# Example_A.net
KiCad netlist of a schematic drawn in EAGLE
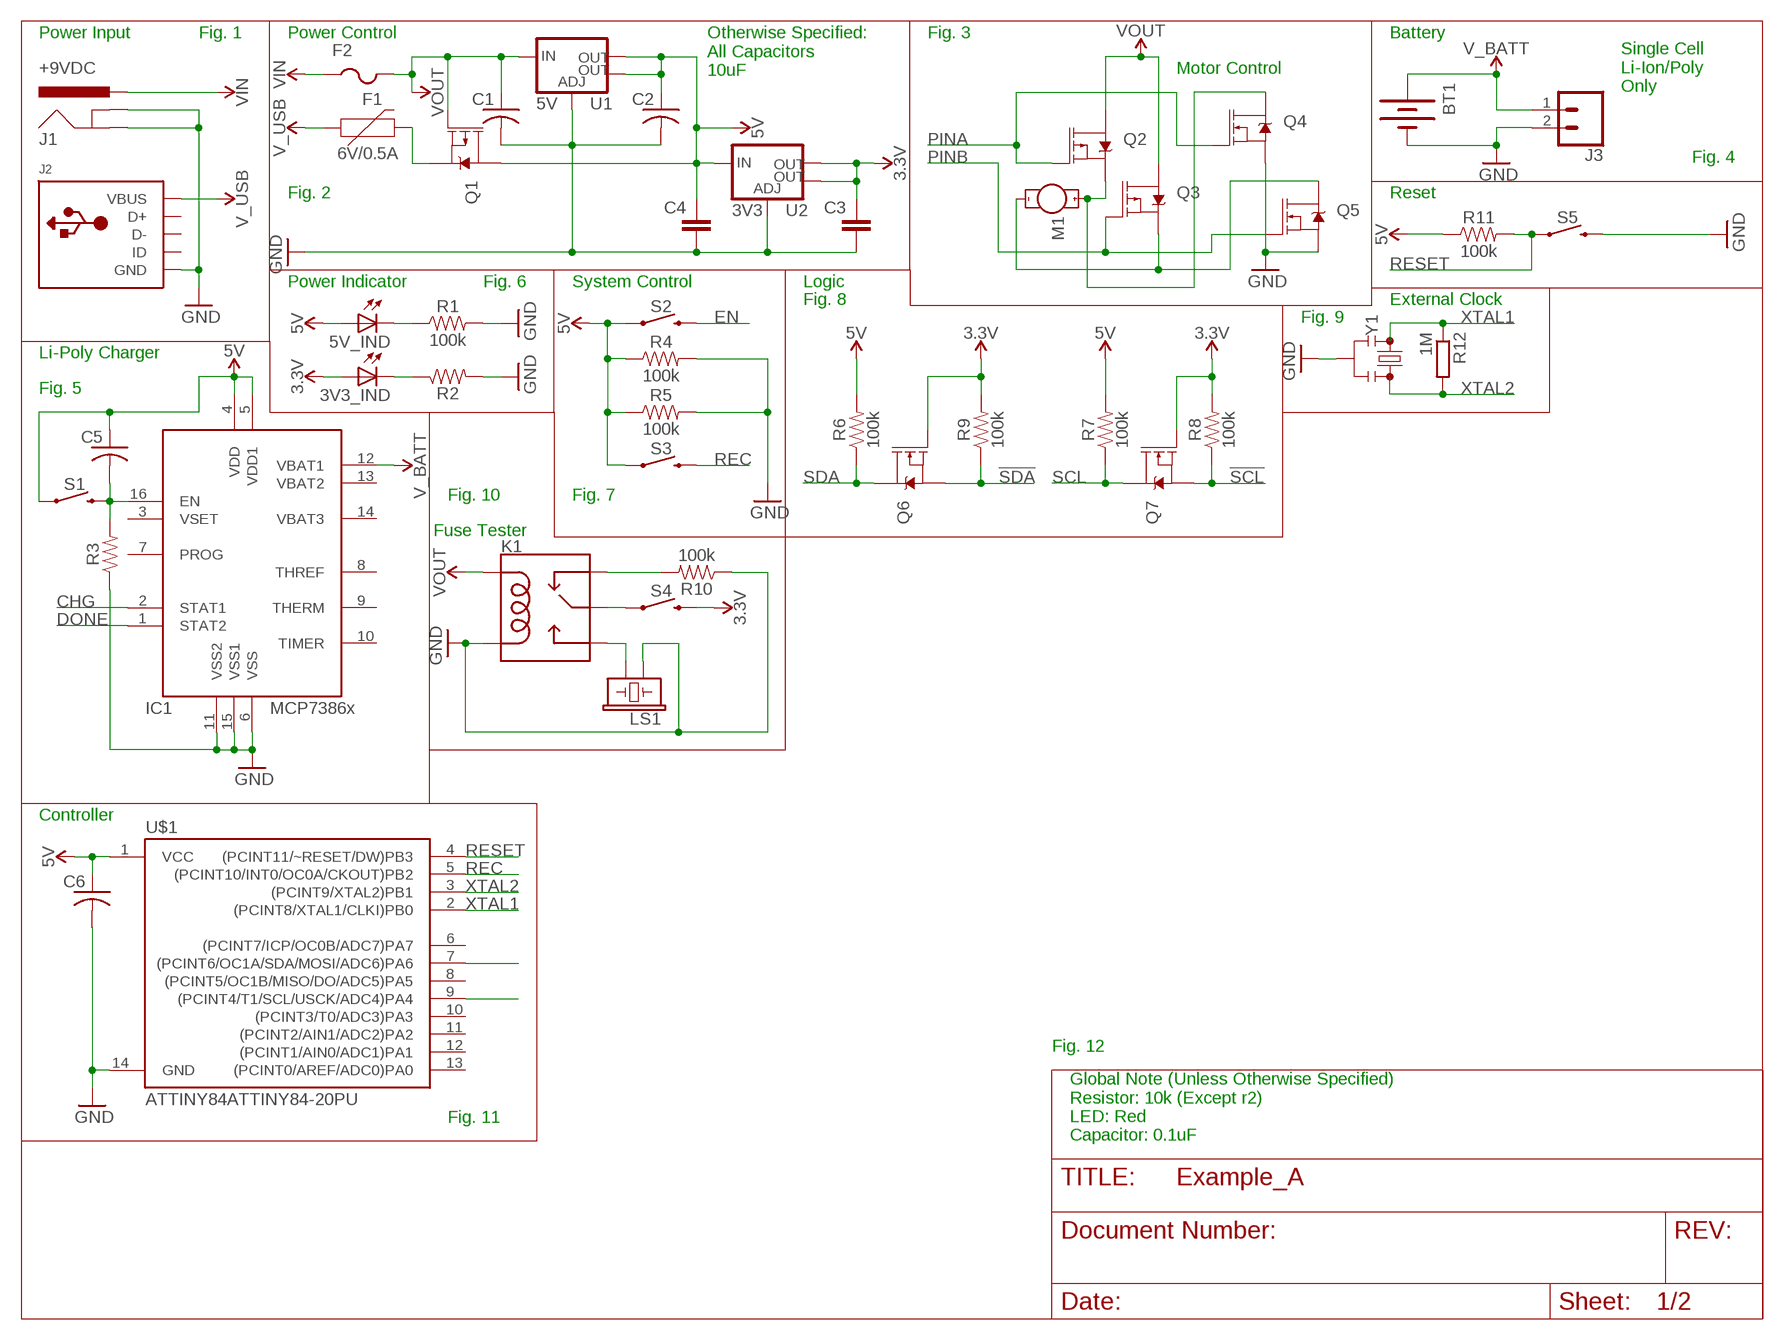
[diagram p0: schematic, sheet 1]
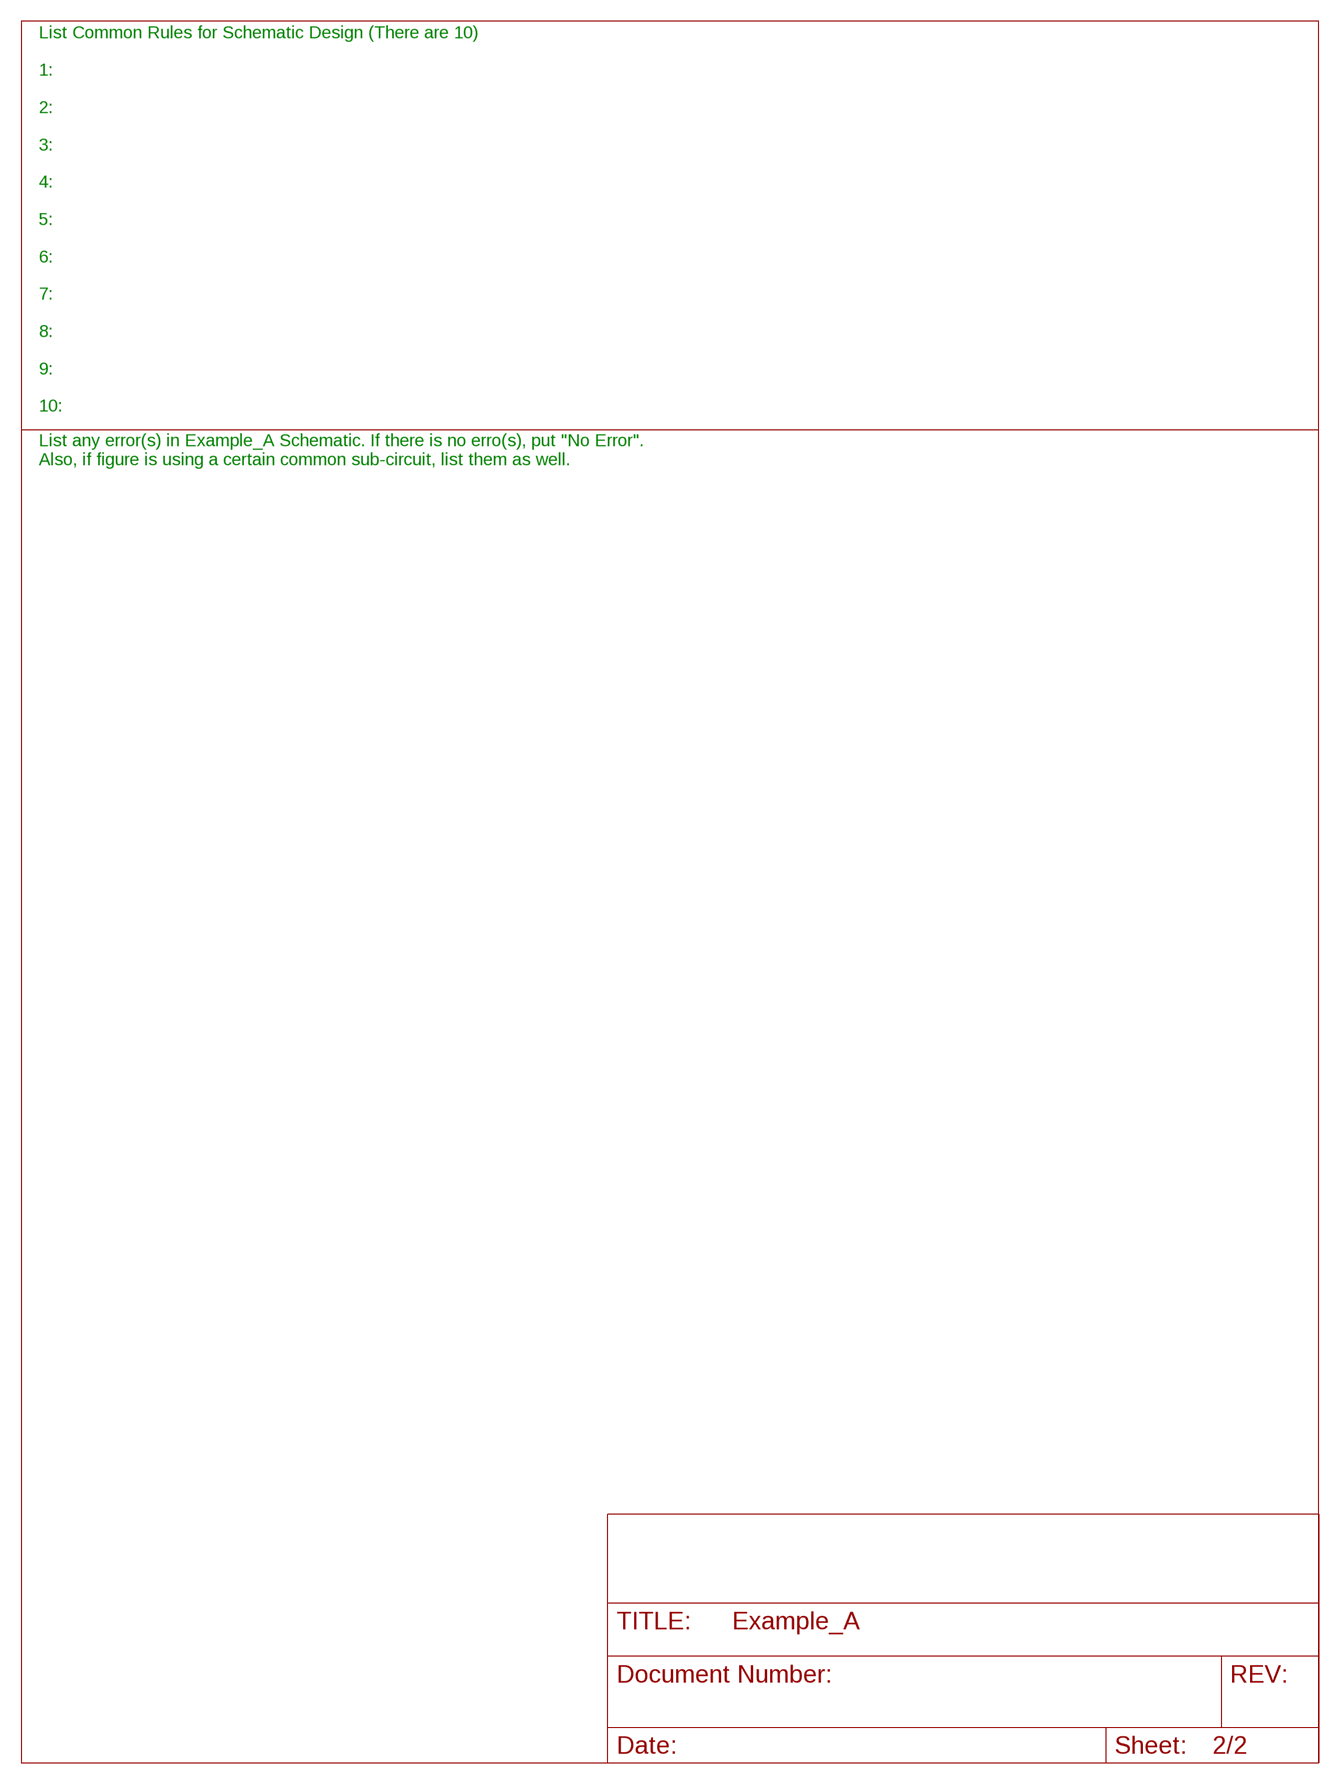
[diagram p1: schematic, sheet 2]

(export (version "E")
  (design (tool "Eeschema 10.0.6"))
  (components
    (comp (ref "3V3_IND")
      (value "LEDCHIP-LED0805")
      (footprint "eagle-import:CHIP-LED0805")
      (libsource (lib "eagle-import") (part "LEDCHIP-LED0805"))
    )
    (comp (ref "5V_IND")
      (value "LEDCHIP-LED0805")
      (footprint "eagle-import:CHIP-LED0805")
      (libsource (lib "eagle-import") (part "LEDCHIP-LED0805"))
    )
    (comp (ref "BT1")
      (value "BATTERYFOB")
      (footprint "eagle-import:BATTERY_20MM_PTH_COMPACT")
      (libsource (lib "eagle-import") (part "BATTERYFOB"))
    )
    (comp (ref "C1")
      (value "C-USC0805")
      (footprint "eagle-import:C0805")
      (libsource (lib "eagle-import") (part "C-USC0805"))
    )
    (comp (ref "C2")
      (value "C-USC0805")
      (footprint "eagle-import:C0805")
      (libsource (lib "eagle-import") (part "C-USC0805"))
    )
    (comp (ref "C3")
      (value "C-EUC0805")
      (footprint "eagle-import:C0805")
      (libsource (lib "eagle-import") (part "C-EUC0805"))
    )
    (comp (ref "C4")
      (value "C-EUC0805")
      (footprint "eagle-import:C0805")
      (libsource (lib "eagle-import") (part "C-EUC0805"))
    )
    (comp (ref "C5")
      (value "C-USC0805")
      (footprint "eagle-import:C0805")
      (libsource (lib "eagle-import") (part "C-USC0805"))
    )
    (comp (ref "C6")
      (value "C-USC0805")
      (footprint "eagle-import:C0805")
      (libsource (lib "eagle-import") (part "C-USC0805"))
    )
    (comp (ref "F1")
      (value "6V/0.5A")
      (footprint "eagle-import:1206")
      (libsource (lib "eagle-import") (part "PPTC_HALF-AMP"))
    )
    (comp (ref "F2")
      (value "PTCFUSE-1206")
      (footprint "eagle-import:R1206")
      (libsource (lib "eagle-import") (part "PTCFUSE-1206"))
    )
    (comp (ref "IC1")
      (value "MCP7386XS")
      (footprint "eagle-import:SO16")
      (libsource (lib "eagle-import") (part "MCP7386XS"))
    )
    (comp (ref "J1")
      (value "+9VDC")
      (footprint "eagle-import:POWER_JACK_SMD")
      (libsource (lib "eagle-import") (part "POWER_JACKSMD"))
    )
    (comp (ref "J2")
      (value "USBMINIB")
      (footprint "eagle-import:USB-MINIB")
      (libsource (lib "eagle-import") (part "USBMINIB"))
    )
    (comp (ref "J3")
      (value "CONN_023.5MM_LOCK")
      (footprint "eagle-import:SCREWTERMINAL-3.5MM-2_LOCK")
      (libsource (lib "eagle-import") (part "CONN_023.5MM_LOCK"))
    )
    (comp (ref "K1")
      (value "RELAY-SPDT-JZC-11F")
      (footprint "eagle-import:RELAY-JZC")
      (libsource (lib "eagle-import") (part "RELAY-SPDT-JZC-11F"))
    )
    (comp (ref "LS1")
      (value "BUZZER-PTH")
      (footprint "eagle-import:BUZZER-12MM")
      (libsource (lib "eagle-import") (part "BUZZER-PTH"))
    )
    (comp (ref "M1")
      (value "MOTOR10MM")
      (footprint "eagle-import:VIBE-MOTOR-10MM")
      (libsource (lib "eagle-import") (part "MOTOR10MM"))
    )
    (comp (ref "Q1")
      (value "MOSFET_PCH-SI2309DS")
      (footprint "eagle-import:SOT23-3")
      (libsource (lib "eagle-import") (part "MOSFET_PCH-SI2309DS"))
    )
    (comp (ref "Q2")
      (value "MOSFET_PCH-SI2309DS")
      (footprint "eagle-import:SOT23-3")
      (libsource (lib "eagle-import") (part "MOSFET_PCH-SI2309DS"))
    )
    (comp (ref "Q3")
      (value "MOSFET_PCH-SI2309DS")
      (footprint "eagle-import:SOT23-3")
      (libsource (lib "eagle-import") (part "MOSFET_PCH-SI2309DS"))
    )
    (comp (ref "Q4")
      (value "MOSFET-NCH-PSMN7R0")
      (footprint "eagle-import:TO-263_D2PAK")
      (libsource (lib "eagle-import") (part "MOSFET-NCH-PSMN7R0"))
    )
    (comp (ref "Q5")
      (value "MOSFET-NCH-PSMN7R0")
      (footprint "eagle-import:TO-263_D2PAK")
      (libsource (lib "eagle-import") (part "MOSFET-NCH-PSMN7R0"))
    )
    (comp (ref "Q6")
      (value "MOSFET-NCH-FQP30N06L")
      (footprint "eagle-import:TO220V")
      (libsource (lib "eagle-import") (part "MOSFET-NCH-FQP30N06L"))
    )
    (comp (ref "Q7")
      (value "MOSFET-NCH-FQP30N06L")
      (footprint "eagle-import:TO220V")
      (libsource (lib "eagle-import") (part "MOSFET-NCH-FQP30N06L"))
    )
    (comp (ref "R1")
      (value "100k")
      (footprint "eagle-import:0805")
      (libsource (lib "eagle-import") (part "RESISTOR0805"))
    )
    (comp (ref "R2")
      (value "RESISTOR0805")
      (footprint "eagle-import:0805")
      (libsource (lib "eagle-import") (part "RESISTOR0805"))
    )
    (comp (ref "R3")
      (value "RESISTOR0805")
      (footprint "eagle-import:0805")
      (libsource (lib "eagle-import") (part "RESISTOR0805"))
    )
    (comp (ref "R4")
      (value "100k")
      (footprint "eagle-import:0805")
      (libsource (lib "eagle-import") (part "RESISTOR0805"))
    )
    (comp (ref "R5")
      (value "100k")
      (footprint "eagle-import:0805")
      (libsource (lib "eagle-import") (part "RESISTOR0805"))
    )
    (comp (ref "R6")
      (value "100k")
      (footprint "eagle-import:0805")
      (libsource (lib "eagle-import") (part "RESISTOR0805"))
    )
    (comp (ref "R7")
      (value "100k")
      (footprint "eagle-import:0805")
      (libsource (lib "eagle-import") (part "RESISTOR0805"))
    )
    (comp (ref "R8")
      (value "100k")
      (footprint "eagle-import:0805")
      (libsource (lib "eagle-import") (part "RESISTOR0805"))
    )
    (comp (ref "R9")
      (value "100k")
      (footprint "eagle-import:0805")
      (libsource (lib "eagle-import") (part "RESISTOR0805"))
    )
    (comp (ref "R10")
      (value "100k")
      (footprint "eagle-import:0805")
      (libsource (lib "eagle-import") (part "RESISTOR0805"))
    )
    (comp (ref "R11")
      (value "100k")
      (footprint "eagle-import:0805")
      (libsource (lib "eagle-import") (part "RESISTOR0805"))
    )
    (comp (ref "R12")
      (value "1M")
      (footprint "eagle-import:R0805")
      (libsource (lib "eagle-import") (part "R-EU_R0805"))
    )
    (comp (ref "S1")
      (value "MOMENTARY-SWITCH-SPST-SMD-RIGHT-ANGLE")
      (footprint "eagle-import:TACTILE_SWITCH_SMD_RIGHT_ANGLE")
      (libsource (lib "eagle-import") (part "MOMENTARY-SWITCH-SPST-SMD-RIGHT-ANGLE"))
    )
    (comp (ref "S2")
      (value "MOMENTARY-SWITCH-SPST-SMD-RIGHT-ANGLE")
      (footprint "eagle-import:TACTILE_SWITCH_SMD_RIGHT_ANGLE")
      (libsource (lib "eagle-import") (part "MOMENTARY-SWITCH-SPST-SMD-RIGHT-ANGLE"))
    )
    (comp (ref "S3")
      (value "MOMENTARY-SWITCH-SPST-SMD-RIGHT-ANGLE")
      (footprint "eagle-import:TACTILE_SWITCH_SMD_RIGHT_ANGLE")
      (libsource (lib "eagle-import") (part "MOMENTARY-SWITCH-SPST-SMD-RIGHT-ANGLE"))
    )
    (comp (ref "S4")
      (value "MOMENTARY-SWITCH-SPST-SMD-RIGHT-ANGLE")
      (footprint "eagle-import:TACTILE_SWITCH_SMD_RIGHT_ANGLE")
      (libsource (lib "eagle-import") (part "MOMENTARY-SWITCH-SPST-SMD-RIGHT-ANGLE"))
    )
    (comp (ref "S5")
      (value "MOMENTARY-SWITCH-SPST-SMD-RIGHT-ANGLE")
      (footprint "eagle-import:TACTILE_SWITCH_SMD_RIGHT_ANGLE")
      (libsource (lib "eagle-import") (part "MOMENTARY-SWITCH-SPST-SMD-RIGHT-ANGLE"))
    )
    (comp (ref "U$1")
      (value "ATTINY84ATTINY84-20PU")
      (footprint "eagle-import:DIP14")
      (libsource (lib "eagle-import") (part "ATTINY84ATTINY84-20PU"))
    )
    (comp (ref "U1")
      (value "5V")
      (footprint "eagle-import:SOT223")
      (libsource (lib "eagle-import") (part "V_REG_LM1117SOT223"))
    )
    (comp (ref "U2")
      (value "3V3")
      (footprint "eagle-import:SOT223")
      (libsource (lib "eagle-import") (part "V_REG_LM1117SOT223"))
    )
    (comp (ref "Y1")
      (value "RESONATORSMD-7.4X3.4")
      (footprint "eagle-import:RESONATOR-SMD-7.4X3.4")
      (libsource (lib "eagle-import") (part "RESONATORSMD-7.4X3.4"))
    )
  )
  (nets
    (net (code "1") (name "3.3V") (class "Default")
      (node (ref "3V3_IND") (pin "A") (pinfunction "A_A") (pintype "passive"))
      (node (ref "C3") (pin "1") (pinfunction "1_1") (pintype "passive"))
      (node (ref "Q6") (pin "1") (pinfunction "G_1") (pintype "bidirectional"))
      (node (ref "Q7") (pin "1") (pinfunction "G_1") (pintype "bidirectional"))
      (node (ref "R8") (pin "2") (pinfunction "2_2") (pintype "passive"))
      (node (ref "R9") (pin "2") (pinfunction "2_2") (pintype "passive"))
      (node (ref "S4") (pin "2") (pinfunction "2_2") (pintype "passive"))
      (node (ref "U2") (pin "2") (pinfunction "OUT_2") (pintype "output"))
      (node (ref "U2") (pin "4") (pinfunction "OUT_4") (pintype "output"))
    )
    (net (code "2") (name "5V") (class "Default")
      (node (ref "5V_IND") (pin "A") (pinfunction "A_A") (pintype "passive"))
      (node (ref "C2") (pin "1") (pinfunction "1_1") (pintype "passive"))
      (node (ref "C4") (pin "1") (pinfunction "1_1") (pintype "passive"))
      (node (ref "C5") (pin "1") (pinfunction "1_1") (pintype "passive"))
      (node (ref "C6") (pin "1") (pinfunction "1_1") (pintype "passive"))
      (node (ref "IC1") (pin "4") (pinfunction "VDD_4") (pintype "power_in"))
      (node (ref "IC1") (pin "5") (pinfunction "VDD1_5") (pintype "power_in"))
      (node (ref "Q1") (pin "3") (pinfunction "D_3") (pintype "bidirectional"))
      (node (ref "R11") (pin "1") (pinfunction "1_1") (pintype "passive"))
      (node (ref "R4") (pin "1") (pinfunction "1_1") (pintype "passive"))
      (node (ref "R5") (pin "1") (pinfunction "1_1") (pintype "passive"))
      (node (ref "R6") (pin "2") (pinfunction "2_2") (pintype "passive"))
      (node (ref "R7") (pin "2") (pinfunction "2_2") (pintype "passive"))
      (node (ref "S1") (pin "1") (pinfunction "1_1") (pintype "passive"))
      (node (ref "S2") (pin "1") (pinfunction "1_1") (pintype "passive"))
      (node (ref "S3") (pin "1") (pinfunction "1_1") (pintype "passive"))
      (node (ref "U$1") (pin "1") (pinfunction "VCC_1") (pintype "bidirectional"))
      (node (ref "U1") (pin "2") (pinfunction "OUT_2") (pintype "output"))
      (node (ref "U1") (pin "4") (pinfunction "OUT_4") (pintype "output"))
      (node (ref "U2") (pin "3") (pinfunction "IN_3") (pintype "input"))
    )
    (net (code "3") (name "CHG") (class "Default")
      (node (ref "IC1") (pin "2") (pinfunction "STAT1_2") (pintype "output"))
    )
    (net (code "4") (name "DONE") (class "Default")
      (node (ref "IC1") (pin "1") (pinfunction "STAT2_1") (pintype "output"))
    )
    (net (code "5") (name "EN") (class "Default")
      (node (ref "S2") (pin "2") (pinfunction "2_2") (pintype "passive"))
    )
    (net (code "6") (name "GND") (class "Default")
      (node (ref "BT1") (pin "2") (pinfunction "-_2") (pintype "power_in"))
      (node (ref "C1") (pin "2") (pinfunction "2_2") (pintype "passive"))
      (node (ref "C2") (pin "2") (pinfunction "2_2") (pintype "passive"))
      (node (ref "C3") (pin "2") (pinfunction "2_2") (pintype "passive"))
      (node (ref "C4") (pin "2") (pinfunction "2_2") (pintype "passive"))
      (node (ref "C6") (pin "2") (pinfunction "2_2") (pintype "passive"))
      (node (ref "IC1") (pin "11") (pinfunction "VSS2_11") (pintype "power_in"))
      (node (ref "IC1") (pin "15") (pinfunction "VSS1_15") (pintype "power_in"))
      (node (ref "IC1") (pin "6") (pinfunction "VSS_6") (pintype "power_in"))
      (node (ref "J1") (pin "GND") (pinfunction "GNDBREAK_GND") (pintype "bidirectional"))
      (node (ref "J1") (pin "P$4") (pinfunction "GND_P$4") (pintype "bidirectional"))
      (node (ref "J2") (pin "GND") (pinfunction "GND_GND") (pintype "power_in"))
      (node (ref "J3") (pin "2") (pinfunction "2_2") (pintype "passive"))
      (node (ref "K1") (pin "1") (pinfunction "COIL2_1") (pintype "bidirectional"))
      (node (ref "LS1") (pin "+") (pinfunction "1_+") (pintype "passive"))
      (node (ref "Q4") (pin "3") (pinfunction "S_3") (pintype "bidirectional"))
      (node (ref "Q5") (pin "3") (pinfunction "S_3") (pintype "bidirectional"))
      (node (ref "R1") (pin "2") (pinfunction "2_2") (pintype "passive"))
      (node (ref "R10") (pin "1") (pinfunction "1_1") (pintype "passive"))
      (node (ref "R2") (pin "2") (pinfunction "2_2") (pintype "passive"))
      (node (ref "R3") (pin "1") (pinfunction "1_1") (pintype "passive"))
      (node (ref "R4") (pin "2") (pinfunction "2_2") (pintype "passive"))
      (node (ref "R5") (pin "2") (pinfunction "2_2") (pintype "passive"))
      (node (ref "S5") (pin "2") (pinfunction "2_2") (pintype "passive"))
      (node (ref "U$1") (pin "14") (pinfunction "GND_14") (pintype "bidirectional"))
      (node (ref "U1") (pin "1") (pinfunction "ADJ_1") (pintype "input"))
      (node (ref "U2") (pin "1") (pinfunction "ADJ_1") (pintype "input"))
      (node (ref "Y1") (pin "2") (pinfunction "2_2") (pintype "passive"))
    )
    (net (code "7") (name "Net-(3V3_IND-PadC)") (class "Default")
      (node (ref "3V3_IND") (pin "C") (pinfunction "C_C") (pintype "passive"))
      (node (ref "R2") (pin "1") (pinfunction "1_1") (pintype "passive"))
    )
    (net (code "8") (name "Net-(5V_IND-PadC)") (class "Default")
      (node (ref "5V_IND") (pin "C") (pinfunction "C_C") (pintype "passive"))
      (node (ref "R1") (pin "1") (pinfunction "1_1") (pintype "passive"))
    )
    (net (code "9") (name "Net-(IC1-EN)") (class "Default")
      (node (ref "C5") (pin "2") (pinfunction "2_2") (pintype "passive"))
      (node (ref "IC1") (pin "16") (pinfunction "EN_16") (pintype "input"))
      (node (ref "R3") (pin "2") (pinfunction "2_2") (pintype "passive"))
      (node (ref "S1") (pin "2") (pinfunction "2_2") (pintype "passive"))
    )
    (net (code "10") (name "Net-(K1-MAIN)") (class "Default")
      (node (ref "K1") (pin "4") (pinfunction "MAIN_4") (pintype "bidirectional"))
      (node (ref "S4") (pin "1") (pinfunction "1_1") (pintype "passive"))
    )
    (net (code "11") (name "Net-(K1-NC)") (class "Default")
      (node (ref "K1") (pin "2") (pinfunction "NC_2") (pintype "bidirectional"))
      (node (ref "R10") (pin "2") (pinfunction "2_2") (pintype "passive"))
    )
    (net (code "12") (name "Net-(K1-NO)") (class "Default")
      (node (ref "K1") (pin "3") (pinfunction "NO_3") (pintype "bidirectional"))
      (node (ref "LS1") (pin "-") (pinfunction "2_-") (pintype "passive"))
    )
    (net (code "13") (name "Net-(Q1-S)") (class "Default")
      (node (ref "F1") (pin "2") (pinfunction "2_2") (pintype "bidirectional"))
      (node (ref "Q1") (pin "2") (pinfunction "S_2") (pintype "bidirectional"))
    )
    (net (code "14") (name "Net-(Q2-S)") (class "Default")
      (node (ref "M1") (pin "+") (pinfunction "+_+") (pintype "bidirectional"))
      (node (ref "Q2") (pin "2") (pinfunction "S_2") (pintype "bidirectional"))
      (node (ref "Q4") (pin "2") (pinfunction "D_2") (pintype "bidirectional"))
    )
    (net (code "15") (name "Net-(Q3-S)") (class "Default")
      (node (ref "M1") (pin "-") (pinfunction "-_-") (pintype "bidirectional"))
      (node (ref "Q3") (pin "2") (pinfunction "S_2") (pintype "bidirectional"))
      (node (ref "Q5") (pin "2") (pinfunction "D_2") (pintype "bidirectional"))
    )
    (net (code "16") (name "PINA") (class "Default")
      (node (ref "Q2") (pin "1") (pinfunction "G_1") (pintype "bidirectional"))
      (node (ref "Q4") (pin "1") (pinfunction "G_1") (pintype "bidirectional"))
    )
    (net (code "17") (name "PINB") (class "Default")
      (node (ref "Q3") (pin "1") (pinfunction "G_1") (pintype "bidirectional"))
      (node (ref "Q5") (pin "1") (pinfunction "G_1") (pintype "bidirectional"))
    )
    (net (code "18") (name "REC") (class "Default")
      (node (ref "S3") (pin "2") (pinfunction "2_2") (pintype "passive"))
      (node (ref "U$1") (pin "5") (pinfunction "(PCINT10/INT0/OC0A/CKOUT)PB2_5") (pintype "bidirectional"))
    )
    (net (code "19") (name "RESET") (class "Default")
      (node (ref "R11") (pin "2") (pinfunction "2_2") (pintype "passive"))
      (node (ref "S5") (pin "1") (pinfunction "1_1") (pintype "passive"))
      (node (ref "U$1") (pin "4") (pinfunction "(PCINT11/~{RESET/DW})PB3_4") (pintype "bidirectional"))
    )
    (net (code "20") (name "SCL") (class "Default")
      (node (ref "Q7") (pin "2") (pinfunction "D_2") (pintype "bidirectional"))
      (node (ref "R7") (pin "1") (pinfunction "1_1") (pintype "passive"))
    )
    (net (code "21") (name "SDA") (class "Default")
      (node (ref "Q6") (pin "2") (pinfunction "D_2") (pintype "bidirectional"))
      (node (ref "R6") (pin "1") (pinfunction "1_1") (pintype "passive"))
    )
    (net (code "22") (name "VIN") (class "Default")
      (node (ref "F2") (pin "1") (pinfunction "1_1") (pintype "passive"))
      (node (ref "J1") (pin "VIN0") (pinfunction "PWR_VIN0") (pintype "bidirectional"))
    )
    (net (code "23") (name "VOUT") (class "Default")
      (node (ref "C1") (pin "1") (pinfunction "1_1") (pintype "passive"))
      (node (ref "F2") (pin "2") (pinfunction "2_2") (pintype "passive"))
      (node (ref "K1") (pin "5") (pinfunction "COIL1_5") (pintype "bidirectional"))
      (node (ref "Q1") (pin "1") (pinfunction "G_1") (pintype "bidirectional"))
      (node (ref "Q2") (pin "3") (pinfunction "D_3") (pintype "bidirectional"))
      (node (ref "Q3") (pin "3") (pinfunction "D_3") (pintype "bidirectional"))
      (node (ref "U1") (pin "3") (pinfunction "IN_3") (pintype "input"))
    )
    (net (code "24") (name "V_BATT") (class "Default")
      (node (ref "BT1") (pin "1") (pinfunction "+_1") (pintype "power_in"))
      (node (ref "IC1") (pin "12") (pinfunction "VBAT1_12") (pintype "input"))
      (node (ref "J3") (pin "1") (pinfunction "1_1") (pintype "passive"))
    )
    (net (code "25") (name "V_USB") (class "Default")
      (node (ref "F1") (pin "1") (pinfunction "1_1") (pintype "bidirectional"))
      (node (ref "J2") (pin "VBUS") (pinfunction "VBUS_VBUS") (pintype "power_in"))
    )
    (net (code "26") (name "XTAL1") (class "Default")
      (node (ref "R12") (pin "1") (pinfunction "1_1") (pintype "passive"))
      (node (ref "U$1") (pin "2") (pinfunction "(PCINT8/XTAL1/CLKI)PB0_2") (pintype "bidirectional"))
      (node (ref "Y1") (pin "1") (pinfunction "1_1") (pintype "passive"))
    )
    (net (code "27") (name "XTAL2") (class "Default")
      (node (ref "R12") (pin "2") (pinfunction "2_2") (pintype "passive"))
      (node (ref "U$1") (pin "3") (pinfunction "(PCINT9/XTAL2)PB1_3") (pintype "bidirectional"))
      (node (ref "Y1") (pin "3") (pinfunction "3_3") (pintype "passive"))
    )
    (net (code "28") (name "unconnected-(IC1-PROG-Pad7)") (class "Default")
      (node (ref "IC1") (pin "7") (pinfunction "PROG_7") (pintype "passive"))
    )
    (net (code "29") (name "unconnected-(IC1-THERM-Pad9)") (class "Default")
      (node (ref "IC1") (pin "9") (pinfunction "THERM_9") (pintype "passive"))
    )
    (net (code "30") (name "unconnected-(IC1-THREF-Pad8)") (class "Default")
      (node (ref "IC1") (pin "8") (pinfunction "THREF_8") (pintype "passive"))
    )
    (net (code "31") (name "unconnected-(IC1-TIMER-Pad10)") (class "Default")
      (node (ref "IC1") (pin "10") (pinfunction "TIMER_10") (pintype "passive"))
    )
    (net (code "32") (name "unconnected-(IC1-VBAT2-Pad13)") (class "Default")
      (node (ref "IC1") (pin "13") (pinfunction "VBAT2_13") (pintype "input"))
    )
    (net (code "33") (name "unconnected-(IC1-VBAT3-Pad14)") (class "Default")
      (node (ref "IC1") (pin "14") (pinfunction "VBAT3_14") (pintype "input"))
    )
    (net (code "34") (name "unconnected-(IC1-VSET-Pad3)") (class "Default")
      (node (ref "IC1") (pin "3") (pinfunction "VSET_3") (pintype "input"))
    )
    (net (code "35") (name "unconnected-(J2-PadD+)") (class "Default")
      (node (ref "J2") (pin "D+") (pinfunction "D+_D+") (pintype "bidirectional"))
    )
    (net (code "36") (name "unconnected-(J2-PadD-)") (class "Default")
      (node (ref "J2") (pin "D-") (pinfunction "D-_D-") (pintype "bidirectional"))
    )
    (net (code "37") (name "unconnected-(J2-PadID)") (class "Default")
      (node (ref "J2") (pin "ID") (pinfunction "ID_ID") (pintype "bidirectional"))
    )
    (net (code "38") (name "unconnected-(U$1-(PCINT0{slash}AREF{slash}ADC0)PA0-Pad13)") (class "Default")
      (node (ref "U$1") (pin "13") (pinfunction "(PCINT0/AREF/ADC0)PA0_13") (pintype "bidirectional"))
    )
    (net (code "39") (name "unconnected-(U$1-(PCINT1{slash}AIN0{slash}ADC1)PA1-Pad12)") (class "Default")
      (node (ref "U$1") (pin "12") (pinfunction "(PCINT1/AIN0/ADC1)PA1_12") (pintype "bidirectional"))
    )
    (net (code "40") (name "unconnected-(U$1-(PCINT2{slash}AIN1{slash}ADC2)PA2-Pad11)") (class "Default")
      (node (ref "U$1") (pin "11") (pinfunction "(PCINT2/AIN1/ADC2)PA2_11") (pintype "bidirectional"))
    )
    (net (code "41") (name "unconnected-(U$1-(PCINT3{slash}T0{slash}ADC3)PA3-Pad10)") (class "Default")
      (node (ref "U$1") (pin "10") (pinfunction "(PCINT3/T0/ADC3)PA3_10") (pintype "bidirectional"))
    )
    (net (code "42") (name "unconnected-(U$1-(PCINT4{slash}T1{slash}SCL{slash}USCK{slash}ADC4)PA4-Pad9)") (class "Default")
      (node (ref "U$1") (pin "9") (pinfunction "(PCINT4/T1/SCL/USCK/ADC4)PA4_9") (pintype "bidirectional"))
    )
    (net (code "43") (name "unconnected-(U$1-(PCINT5{slash}OC1B{slash}MISO{slash}DO{slash}ADC5)PA5-Pad8)") (class "Default")
      (node (ref "U$1") (pin "8") (pinfunction "(PCINT5/OC1B/MISO/DO/ADC5)PA5_8") (pintype "bidirectional"))
    )
    (net (code "44") (name "unconnected-(U$1-(PCINT6{slash}OC1A{slash}SDA{slash}MOSI{slash}ADC6)PA6-Pad7)") (class "Default")
      (node (ref "U$1") (pin "7") (pinfunction "(PCINT6/OC1A/SDA/MOSI/ADC6)PA6_7") (pintype "bidirectional"))
    )
    (net (code "45") (name "unconnected-(U$1-(PCINT7{slash}ICP{slash}OC0B{slash}ADC7)PA7-Pad6)") (class "Default")
      (node (ref "U$1") (pin "6") (pinfunction "(PCINT7/ICP/OC0B/ADC7)PA7_6") (pintype "bidirectional"))
    )
    (net (code "46") (name "~{SCL}") (class "Default")
      (node (ref "Q7") (pin "3") (pinfunction "S_3") (pintype "bidirectional"))
      (node (ref "R8") (pin "1") (pinfunction "1_1") (pintype "passive"))
    )
    (net (code "47") (name "~{SDA}") (class "Default")
      (node (ref "Q6") (pin "3") (pinfunction "S_3") (pintype "bidirectional"))
      (node (ref "R9") (pin "1") (pinfunction "1_1") (pintype "passive"))
    )
  )
)
